# opg_psu.net
KiCad netlist of a schematic drawn in Altium Designer
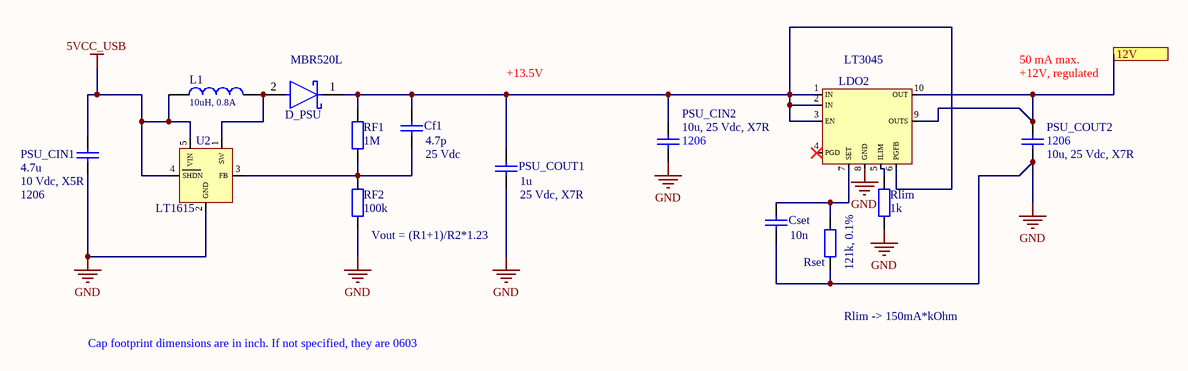
[diagram p0: opg_psu.SchDoc]

(export (version "E")
  (design (tool "Eeschema 10.0.6"))
  (components
    (comp (ref "Cf1")
      (value "4.7p")
      (footprint "1608[0603]")
      (description "Capacitor (Semiconductor SIM Model)")
      (fields (field (name "PUBLISHER") "Altium Limited"))
      (libsource (lib "Miscellaneous Devices") (part "Cap Semi"))
    )
    (comp (ref "Cset")
      (value "10n")
      (footprint "1608[0603]")
      (description "Capacitor (Semiconductor SIM Model)")
      (fields (field (name "PUBLISHER") "Altium Limited"))
      (libsource (lib "Miscellaneous Devices") (part "Cap Semi"))
    )
    (comp (ref "D_PSU")
      (value "MBR0540T1G")
      (footprint "On_Semiconductor_425-04_MFG")
      (libsource (lib "Diode_On_Semiconductor_MBR0540T1G_eec") (part "MBR0540T1G"))
    )
    (comp (ref "L1")
      (value "10uH, 0.8A")
      (footprint "WE-PD2_3521")
      (description "WE-PD2 SMT Power Inductor, size 3521, 10uH, 0.8A")
      (fields
        (field (name "MANUFACTURER") "Wurth Elektronik")
        (field (name "MANUFACTURER PART NUMBER") "7447732110")
      )
      (libsource (lib "WE_power_inductor_wound") (part "7447732110"))
    )
    (comp (ref "LDO2")
      (value "LT3045")
      (footprint "LT3045")
      (description "20V, 500mA, Ultralow Noise, Ultrahigh PSRR LDO")
      (libsource (lib "Regulator") (part "LT3045"))
    )
    (comp (ref "PSU_CIN1")
      (value "4.7u")
      (footprint "C1206")
      (description "Capacitor (Semiconductor SIM Model)")
      (fields (field (name "PUBLISHER") "Altium Limited"))
      (libsource (lib "Miscellaneous Devices") (part "Cap Semi"))
    )
    (comp (ref "PSU_CIN2")
      (value "10u, 25 Vdc, X7R")
      (footprint "C1206")
      (description "Capacitor (Semiconductor SIM Model)")
      (fields (field (name "PUBLISHER") "Altium Limited"))
      (libsource (lib "Miscellaneous Devices") (part "Cap Semi"))
    )
    (comp (ref "PSU_COUT1")
      (value "1u")
      (footprint "1608[0603]")
      (description "Capacitor (Semiconductor SIM Model)")
      (fields (field (name "PUBLISHER") "Altium Limited"))
      (libsource (lib "Miscellaneous Devices") (part "Cap Semi"))
    )
    (comp (ref "PSU_COUT2")
      (value "10u, 25 Vdc, X7R")
      (footprint "C1206")
      (description "Capacitor (Semiconductor SIM Model)")
      (fields (field (name "PUBLISHER") "Altium Limited"))
      (libsource (lib "Miscellaneous Devices") (part "Cap Semi"))
    )
    (comp (ref "RF1")
      (value "1M")
      (footprint "WRIS-KSKE_0805")
      (description "WRIS-KSKE SMT Thick Film Resistor, size 0805, 0.1Ohm, 0.33W")
      (fields
        (field (name "MANUFACTURER") "Wurth Elektronik")
        (field (name "MANUFACTURER PART NUMBER") "560050320001")
      )
      (libsource (lib "Wurth_thick_film_resistors") (part "560050320001"))
    )
    (comp (ref "RF2")
      (value "100k")
      (footprint "WRIS-KSKE_0805")
      (description "WRIS-KSKE SMT Thick Film Resistor, size 0805, 0.1Ohm, 0.33W")
      (fields
        (field (name "MANUFACTURER") "Wurth Elektronik")
        (field (name "MANUFACTURER PART NUMBER") "560050320001")
      )
      (libsource (lib "Wurth_thick_film_resistors") (part "560050320001"))
    )
    (comp (ref "Rlim")
      (value "1k")
      (footprint "WRIS-KSKE_0805")
      (description "WRIS-KSKE SMT Thick Film Resistor, size 0805, 0.1Ohm, 0.33W")
      (fields
        (field (name "MANUFACTURER") "Wurth Elektronik")
        (field (name "MANUFACTURER PART NUMBER") "560050320001")
      )
      (libsource (lib "Wurth_thick_film_resistors") (part "560050320001"))
    )
    (comp (ref "Rset")
      (value "121k, 0.1%")
      (footprint "WRIS-KSKE_1206")
      (description "WRIS-KSKE SMT Thick Film Resistor, size 1206, 0.05Ohm, 0.5W")
      (fields
        (field (name "MANUFACTURER") "Wurth Elektronik")
        (field (name "MANUFACTURER PART NUMBER") "560050332001")
      )
      (libsource (lib "Wurth_1206_inch_resistor") (part "560050332001"))
    )
    (comp (ref "U2")
      (value "LT1615")
      (footprint "LT1615")
      (description "Micropower Step-up DC/DC Converter in ThinSOT")
      (libsource (lib "Regulator") (part "LT1615"))
    )
  )
  (nets
    (net (code "1") (name "/12V") (class "Default")
      (node (ref "LDO2") (pin "10") (pinfunction "OUT_10") (pintype "passive"))
      (node (ref "LDO2") (pin "9") (pinfunction "OUTS_9") (pintype "passive"))
      (node (ref "PSU_COUT2") (pin "2") (pinfunction "2_2") (pintype "passive"))
    )
    (net (code "2") (name "5VCC_USB") (class "Default")
      (node (ref "L1") (pin "1") (pinfunction "1_1") (pintype "passive"))
      (node (ref "PSU_CIN1") (pin "2") (pinfunction "2_2") (pintype "passive"))
      (node (ref "U2") (pin "4") (pinfunction "SHDN_4") (pintype "passive"))
      (node (ref "U2") (pin "5") (pinfunction "VIN_5") (pintype "passive"))
    )
    (net (code "3") (name "GND") (class "Default")
      (node (ref "Cset") (pin "1") (pinfunction "1_1") (pintype "passive"))
      (node (ref "LDO2") (pin "8") (pinfunction "GND_8") (pintype "passive"))
      (node (ref "PSU_CIN1") (pin "1") (pinfunction "1_1") (pintype "passive"))
      (node (ref "PSU_CIN2") (pin "1") (pinfunction "1_1") (pintype "passive"))
      (node (ref "PSU_COUT1") (pin "1") (pinfunction "1_1") (pintype "passive"))
      (node (ref "PSU_COUT2") (pin "1") (pinfunction "1_1") (pintype "passive"))
      (node (ref "RF2") (pin "1") (pinfunction "1_1") (pintype "passive"))
      (node (ref "Rlim") (pin "1") (pinfunction "1_1") (pintype "passive"))
      (node (ref "Rset") (pin "1") (pinfunction "1_1") (pintype "passive"))
      (node (ref "U2") (pin "2") (pinfunction "GND_2") (pintype "passive"))
    )
    (net (code "4") (name "Net-(D_PSU-A)") (class "Default")
      (node (ref "D_PSU") (pin "2") (pinfunction "A_2") (pintype "passive"))
      (node (ref "L1") (pin "2") (pinfunction "2_2") (pintype "passive"))
      (node (ref "U2") (pin "1") (pinfunction "SW_1") (pintype "passive"))
    )
    (net (code "5") (name "Net-(D_PSU-C)") (class "Default")
      (node (ref "Cf1") (pin "2") (pinfunction "2_2") (pintype "passive"))
      (node (ref "D_PSU") (pin "1") (pinfunction "C_1") (pintype "passive"))
      (node (ref "LDO2") (pin "1") (pinfunction "IN_1") (pintype "passive"))
      (node (ref "LDO2") (pin "2") (pinfunction "IN_2") (pintype "passive"))
      (node (ref "LDO2") (pin "3") (pinfunction "EN_3") (pintype "passive"))
      (node (ref "LDO2") (pin "6") (pinfunction "PGFB_6") (pintype "passive"))
      (node (ref "PSU_CIN2") (pin "2") (pinfunction "2_2") (pintype "passive"))
      (node (ref "PSU_COUT1") (pin "2") (pinfunction "2_2") (pintype "passive"))
      (node (ref "RF1") (pin "2") (pinfunction "2_2") (pintype "passive"))
    )
    (net (code "6") (name "Net-(LDO2-ILIM)") (class "Default")
      (node (ref "LDO2") (pin "5") (pinfunction "ILIM_5") (pintype "passive"))
      (node (ref "Rlim") (pin "2") (pinfunction "2_2") (pintype "passive"))
    )
    (net (code "7") (name "Net-(LDO2-SET)") (class "Default")
      (node (ref "Cset") (pin "2") (pinfunction "2_2") (pintype "passive"))
      (node (ref "LDO2") (pin "7") (pinfunction "SET_7") (pintype "passive"))
      (node (ref "Rset") (pin "2") (pinfunction "2_2") (pintype "passive"))
    )
    (net (code "8") (name "Net-(U2-FB)") (class "Default")
      (node (ref "Cf1") (pin "1") (pinfunction "1_1") (pintype "passive"))
      (node (ref "RF1") (pin "1") (pinfunction "1_1") (pintype "passive"))
      (node (ref "RF2") (pin "2") (pinfunction "2_2") (pintype "passive"))
      (node (ref "U2") (pin "3") (pinfunction "FB_3") (pintype "passive"))
    )
    (net (code "9") (name "unconnected-(LDO2-PGD-Pad4)") (class "Default")
      (node (ref "LDO2") (pin "4") (pinfunction "PGD_4") (pintype "passive+no_connect"))
    )
  )
)
